# Power.net
KiCad netlist of a schematic drawn in Altium Designer
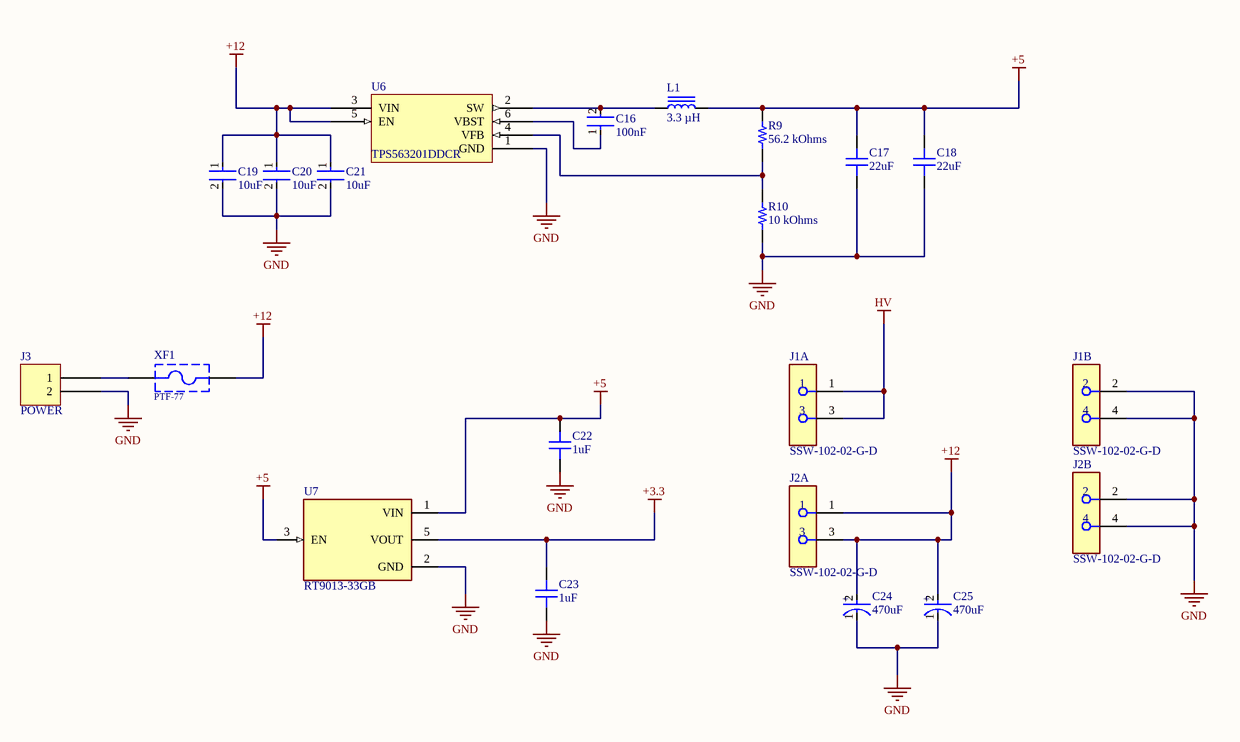
[diagram p0: Power.SchDoc]

(export (version "E")
  (design (tool "Eeschema 10.0.6"))
  (components
    (comp (ref "C16")
      (value "100nF")
      (footprint "FP-C1005-050-0_15-MFG")
      (description "CAP CER 100nF 10V X5R 0402")
      (fields (field (name "TOLERANCE") "20%") (field (name "VOLTAGE") "10V"))
      (libsource (lib "Altium Content Vault") (part "11868f565c42a9108669ba33697ecf6"))
    )
    (comp (ref "C17")
      (value "22uF")
      (footprint "CAP 0603_1608")
      (description "CL10A226MP8NUNE")
      (fields (field (name "PART NUMBER") "C0603C272F3GAC7867") (field (name "MANUFACTURER") "KEMET"))
      (libsource (lib "Celestial Altium Library - altium_library") (part "Capacitor"))
    )
    (comp (ref "C18")
      (value "22uF")
      (footprint "CAP 0603_1608")
      (description "CL10A226MP8NUNE")
      (fields (field (name "PART NUMBER") "C0603C272F3GAC7867") (field (name "MANUFACTURER") "KEMET"))
      (libsource (lib "Celestial Altium Library - altium_library") (part "Capacitor"))
    )
    (comp (ref "C19")
      (value "10uF")
      (footprint "FP-CL21-IPC_B")
      (description "CL21 Series 0805 10uF 16V ±10% Tolerance X5R Multilayer Ceramic Chip Capacitor")
      (fields (field (name "VOLTAGE") "16V") (field (name "TOLERANCE") "10%"))
      (libsource (lib "Altium Content Vault") (part "b4654b650e69147ec39a6b967a45e02"))
    )
    (comp (ref "C20")
      (value "10uF")
      (footprint "FP-CL21-IPC_B")
      (description "CL21 Series 0805 10uF 16V ±10% Tolerance X5R Multilayer Ceramic Chip Capacitor")
      (fields (field (name "VOLTAGE") "16V") (field (name "TOLERANCE") "10%"))
      (libsource (lib "Altium Content Vault") (part "b4654b650e69147ec39a6b967a45e02"))
    )
    (comp (ref "C21")
      (value "10uF")
      (footprint "FP-CL21-IPC_B")
      (description "CL21 Series 0805 10uF 16V ±10% Tolerance X5R Multilayer Ceramic Chip Capacitor")
      (fields (field (name "VOLTAGE") "16V") (field (name "TOLERANCE") "10%"))
      (libsource (lib "Altium Content Vault") (part "b4654b650e69147ec39a6b967a45e02"))
    )
    (comp (ref "C22")
      (value "1uF")
      (footprint "CAP 0603_1608")
      (description "CL10A226MP8NUNE")
      (fields (field (name "PART NUMBER") "C0603C272F3GAC7867") (field (name "MANUFACTURER") "KEMET"))
      (libsource (lib "Celestial Altium Library - altium_library") (part "Capacitor"))
    )
    (comp (ref "C23")
      (value "1uF")
      (footprint "CAP 0603_1608")
      (description "CL10A226MP8NUNE")
      (fields (field (name "PART NUMBER") "C0603C272F3GAC7867") (field (name "MANUFACTURER") "KEMET"))
      (libsource (lib "Celestial Altium Library - altium_library") (part "Capacitor"))
    )
    (comp (ref "C24")
      (value "470uF")
      (footprint "FP-RAD-TH-D_8_0_5-L_15_1-MFG")
      (description "EEUFM1C471L")
      (fields (field (name "TOLERANCE") "20%"))
      (libsource (lib "Altium Content Vault") (part "a00bbbee19879c290e62620ae7e47b1"))
    )
    (comp (ref "C25")
      (value "470uF")
      (footprint "FP-RAD-TH-D_8_0_5-L_15_1-MFG")
      (description "EEUFM1C471L")
      (fields (field (name "TOLERANCE") "20%"))
      (libsource (lib "Altium Content Vault") (part "a00bbbee19879c290e62620ae7e47b1"))
    )
    (comp (ref "J1")
      (value "SSW-102-02-G-D")
      (footprint "FP-SSW-102-02-G-D-MFG")
      (description "CONN RCPT 4POS 0.1 GOLD PCB")
      (libsource (lib "Altium Content Vault") (part "4cb4e83aef2cf044b8f8f0144784ac4"))
    )
    (comp (ref "J2")
      (value "SSW-102-02-G-D")
      (footprint "FP-SSW-102-02-G-D-MFG")
      (description "CONN RCPT 4POS 0.1 GOLD PCB")
      (libsource (lib "Altium Content Vault") (part "4cb4e83aef2cf044b8f8f0144784ac4"))
    )
    (comp (ref "J3")
      (value "POWER")
      (footprint "MOLEX KK 0022272021")
      (description "CONN HEADER VERT 2POS 2.54MM")
      (fields (field (name "PART NUMBER") "0022272021") (field (name "MANUFACTURER") "Molex"))
      (libsource (lib "Celestial Altium Library - altium_library") (part "2 Pin"))
    )
    (comp (ref "L1")
      (value "3.3 µH")
      (footprint "BOURNS SRP5030T")
      (description "MDA5030-3R3M")
      (fields (field (name "PART NUMBER") "SRP5030T-4R7M") (field (name "MANUFACTURER") "Bourns Inc."))
      (libsource (lib "Celestial Altium Library - altium_library") (part "Inductor"))
    )
    (comp (ref "R9")
      (value "56.2 kOhms")
      (footprint "RES 0402_1005")
      (description "RES 110K OHM 1% 1/16W 0402")
      (fields (field (name "PART NUMBER") "RC0402FR-07110KL") (field (name "MANUFACTURER") "Yageo"))
      (libsource (lib "Celestial Altium Library - altium_library") (part "Resistor"))
    )
    (comp (ref "R10")
      (value "10 kOhms")
      (footprint "RES 0402_1005")
      (description "RES 110K OHM 1% 1/16W 0402")
      (fields (field (name "PART NUMBER") "RC0402FR-07110KL") (field (name "MANUFACTURER") "Yageo"))
      (libsource (lib "Celestial Altium Library - altium_library") (part "Resistor"))
    )
    (comp (ref "U6")
      (value "TPS563201DDCR")
      (footprint "SOT23-6_M")
      (libsource (lib "Power") (part "TPS563201DDCR"))
    )
    (comp (ref "U7")
      (value "RT9013-33GB")
      (footprint "RT9013")
      (description "Linear Voltage Regulator IC 1 Output 500mA SOT-23-5")
      (fields (field (name "MF") "Richtek USA"))
      (libsource (lib "Power") (part "RT9013-33GB"))
    )
    (comp (ref "XF1")
      (value "PTF-77")
      (footprint "696107003002")
      (fields
        (field (name "PART NUMBER") "696107003002")
        (field (name "MANUFACTURER") "Wurth Elektronik")
        (field (name "PUBLISHER") "WurthElektronik")
      )
      (libsource (lib "Altium Content Vault") (part "WE-FUSE-2"))
    )
  )
  (nets
    (net (code "1") (name "+3.3") (class "Default")
      (node (ref "C23") (pin "2") (pinfunction "2_2") (pintype "passive"))
      (node (ref "U7") (pin "5") (pinfunction "VOUT_5") (pintype "power_in"))
    )
    (net (code "2") (name "+5") (class "Default")
      (node (ref "C17") (pin "2") (pinfunction "2_2") (pintype "passive"))
      (node (ref "C18") (pin "2") (pinfunction "2_2") (pintype "passive"))
      (node (ref "C22") (pin "2") (pinfunction "2_2") (pintype "passive"))
      (node (ref "L1") (pin "2") (pinfunction "2_2") (pintype "passive"))
      (node (ref "R9") (pin "2") (pinfunction "2_2") (pintype "passive"))
      (node (ref "U7") (pin "1") (pinfunction "VIN_1") (pintype "power_in"))
      (node (ref "U7") (pin "3") (pinfunction "EN_3") (pintype "input"))
    )
    (net (code "3") (name "+12") (class "Default")
      (node (ref "C19") (pin "1") (pinfunction "1_1") (pintype "passive"))
      (node (ref "C20") (pin "1") (pinfunction "1_1") (pintype "passive"))
      (node (ref "C21") (pin "1") (pinfunction "1_1") (pintype "passive"))
      (node (ref "C24") (pin "2") (pinfunction "A_2") (pintype "passive"))
      (node (ref "C25") (pin "2") (pinfunction "A_2") (pintype "passive"))
      (node (ref "J2") (pin "1") (pinfunction "1_1") (pintype "passive"))
      (node (ref "J2") (pin "3") (pinfunction "3_3") (pintype "passive"))
      (node (ref "U6") (pin "3") (pinfunction "VIN_3") (pintype "power_in"))
      (node (ref "U6") (pin "5") (pinfunction "EN_5") (pintype "input"))
      (node (ref "XF1") (pin "2") (pinfunction "2_2") (pintype "passive"))
    )
    (net (code "4") (name "GND") (class "Default")
      (node (ref "C17") (pin "1") (pinfunction "1_1") (pintype "passive"))
      (node (ref "C18") (pin "1") (pinfunction "1_1") (pintype "passive"))
      (node (ref "C19") (pin "2") (pinfunction "2_2") (pintype "passive"))
      (node (ref "C20") (pin "2") (pinfunction "2_2") (pintype "passive"))
      (node (ref "C21") (pin "2") (pinfunction "2_2") (pintype "passive"))
      (node (ref "C22") (pin "1") (pinfunction "1_1") (pintype "passive"))
      (node (ref "C23") (pin "1") (pinfunction "1_1") (pintype "passive"))
      (node (ref "C24") (pin "1") (pinfunction "C_1") (pintype "passive"))
      (node (ref "C25") (pin "1") (pinfunction "C_1") (pintype "passive"))
      (node (ref "J1") (pin "2") (pinfunction "2_2") (pintype "passive"))
      (node (ref "J1") (pin "4") (pinfunction "4_4") (pintype "passive"))
      (node (ref "J2") (pin "2") (pinfunction "2_2") (pintype "passive"))
      (node (ref "J2") (pin "4") (pinfunction "4_4") (pintype "passive"))
      (node (ref "J3") (pin "2") (pinfunction "2_2") (pintype "passive"))
      (node (ref "R10") (pin "1") (pinfunction "1_1") (pintype "passive"))
      (node (ref "U6") (pin "1") (pinfunction "GND_1") (pintype "power_in"))
      (node (ref "U7") (pin "2") (pinfunction "GND_2") (pintype "power_in"))
    )
    (net (code "5") (name "HV") (class "Default")
      (node (ref "J1") (pin "1") (pinfunction "1_1") (pintype "passive"))
      (node (ref "J1") (pin "3") (pinfunction "3_3") (pintype "passive"))
    )
    (net (code "6") (name "Net-(J3-Pad1)") (class "Default")
      (node (ref "J3") (pin "1") (pinfunction "1_1") (pintype "passive"))
      (node (ref "XF1") (pin "1") (pinfunction "1_1") (pintype "passive"))
    )
    (net (code "7") (name "Net-(U6-SW)") (class "Default")
      (node (ref "C16") (pin "2") (pinfunction "2_2") (pintype "passive"))
      (node (ref "L1") (pin "1") (pinfunction "1_1") (pintype "passive"))
      (node (ref "U6") (pin "2") (pinfunction "SW_2") (pintype "output"))
    )
    (net (code "8") (name "Net-(U6-VBST)") (class "Default")
      (node (ref "C16") (pin "1") (pinfunction "1_1") (pintype "passive"))
      (node (ref "U6") (pin "6") (pinfunction "VBST_6") (pintype "input"))
    )
    (net (code "9") (name "Net-(U6-VFB)") (class "Default")
      (node (ref "R10") (pin "2") (pinfunction "2_2") (pintype "passive"))
      (node (ref "R9") (pin "1") (pinfunction "1_1") (pintype "passive"))
      (node (ref "U6") (pin "4") (pinfunction "VFB_4") (pintype "input"))
    )
  )
)
